# Top.net
KiCad netlist of a schematic drawn in Altium Designer
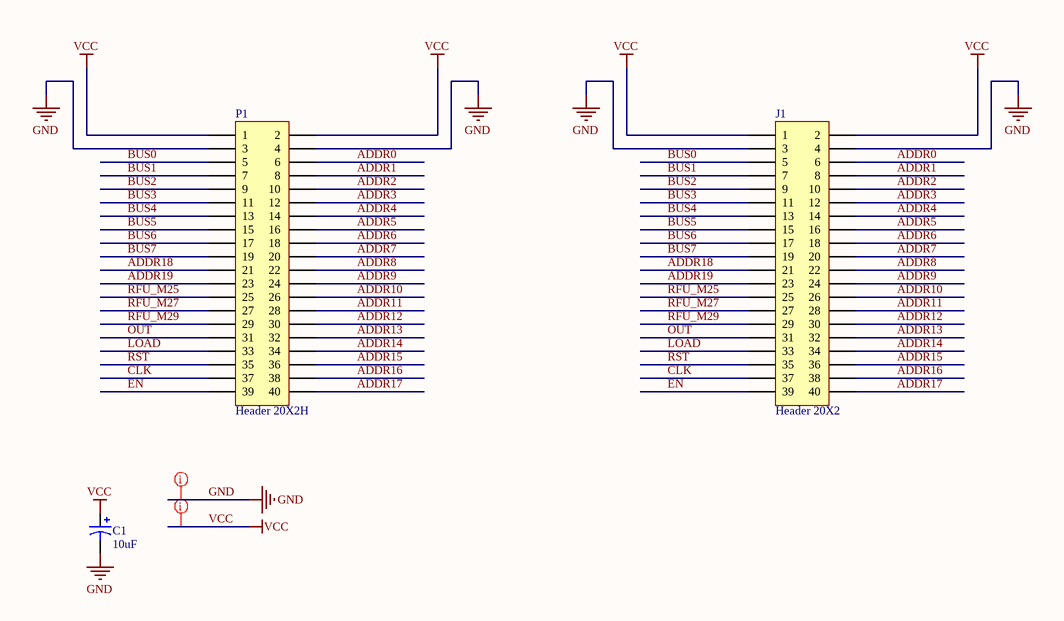
[diagram p0: Top.SchDoc]

(export (version "E")
  (design (tool "Eeschema 10.0.6"))
  (components
    (comp (ref "C1")
      (value "10uF")
      (footprint "C5x7")
      (description "Polarized Capacitor")
      (fields (field (name "Comment") "Cap Pol5") (field (name "PUBLISHER") "Altium Limited"))
      (libsource (lib "Miscellaneous Devices") (part "Cap Pol5"))
    )
    (comp (ref "J1")
      (value "Header 20X2")
      (footprint "HDR2X20")
      (description "Header, 20-Pin, Dual row")
      (fields (field (name "PUBLISHER") "Altium Limited"))
      (libsource (lib "Miscellaneous Connectors") (part "Header 20X2"))
    )
    (comp (ref "P1")
      (value "Header 20X2H")
      (footprint "HDR2X20H")
      (description "Header, 20-Pin, Dual row, Right Angle")
      (fields (field (name "PUBLISHER") "Altium Limited"))
      (libsource (lib "Miscellaneous Connectors") (part "Header 20X2H"))
    )
  )
  (nets
    (net (code "1") (name "/ADDR0") (class "Default")
      (node (ref "J1") (pin "6") (pinfunction "6_6") (pintype "passive"))
      (node (ref "P1") (pin "6") (pinfunction "6_6") (pintype "passive"))
    )
    (net (code "2") (name "/ADDR1") (class "Default")
      (node (ref "J1") (pin "8") (pinfunction "8_8") (pintype "passive"))
      (node (ref "P1") (pin "8") (pinfunction "8_8") (pintype "passive"))
    )
    (net (code "3") (name "/ADDR2") (class "Default")
      (node (ref "J1") (pin "10") (pinfunction "10_10") (pintype "passive"))
      (node (ref "P1") (pin "10") (pinfunction "10_10") (pintype "passive"))
    )
    (net (code "4") (name "/ADDR3") (class "Default")
      (node (ref "J1") (pin "12") (pinfunction "12_12") (pintype "passive"))
      (node (ref "P1") (pin "12") (pinfunction "12_12") (pintype "passive"))
    )
    (net (code "5") (name "/ADDR4") (class "Default")
      (node (ref "J1") (pin "14") (pinfunction "14_14") (pintype "passive"))
      (node (ref "P1") (pin "14") (pinfunction "14_14") (pintype "passive"))
    )
    (net (code "6") (name "/ADDR5") (class "Default")
      (node (ref "J1") (pin "16") (pinfunction "16_16") (pintype "passive"))
      (node (ref "P1") (pin "16") (pinfunction "16_16") (pintype "passive"))
    )
    (net (code "7") (name "/ADDR6") (class "Default")
      (node (ref "J1") (pin "18") (pinfunction "18_18") (pintype "passive"))
      (node (ref "P1") (pin "18") (pinfunction "18_18") (pintype "passive"))
    )
    (net (code "8") (name "/ADDR7") (class "Default")
      (node (ref "J1") (pin "20") (pinfunction "20_20") (pintype "passive"))
      (node (ref "P1") (pin "20") (pinfunction "20_20") (pintype "passive"))
    )
    (net (code "9") (name "/ADDR8") (class "Default")
      (node (ref "J1") (pin "22") (pinfunction "22_22") (pintype "passive"))
      (node (ref "P1") (pin "22") (pinfunction "22_22") (pintype "passive"))
    )
    (net (code "10") (name "/ADDR9") (class "Default")
      (node (ref "J1") (pin "24") (pinfunction "24_24") (pintype "passive"))
      (node (ref "P1") (pin "24") (pinfunction "24_24") (pintype "passive"))
    )
    (net (code "11") (name "/ADDR10") (class "Default")
      (node (ref "J1") (pin "26") (pinfunction "26_26") (pintype "passive"))
      (node (ref "P1") (pin "26") (pinfunction "26_26") (pintype "passive"))
    )
    (net (code "12") (name "/ADDR11") (class "Default")
      (node (ref "J1") (pin "28") (pinfunction "28_28") (pintype "passive"))
      (node (ref "P1") (pin "28") (pinfunction "28_28") (pintype "passive"))
    )
    (net (code "13") (name "/ADDR12") (class "Default")
      (node (ref "J1") (pin "30") (pinfunction "30_30") (pintype "passive"))
      (node (ref "P1") (pin "30") (pinfunction "30_30") (pintype "passive"))
    )
    (net (code "14") (name "/ADDR13") (class "Default")
      (node (ref "J1") (pin "32") (pinfunction "32_32") (pintype "passive"))
      (node (ref "P1") (pin "32") (pinfunction "32_32") (pintype "passive"))
    )
    (net (code "15") (name "/ADDR14") (class "Default")
      (node (ref "J1") (pin "34") (pinfunction "34_34") (pintype "passive"))
      (node (ref "P1") (pin "34") (pinfunction "34_34") (pintype "passive"))
    )
    (net (code "16") (name "/ADDR15") (class "Default")
      (node (ref "J1") (pin "36") (pinfunction "36_36") (pintype "passive"))
      (node (ref "P1") (pin "36") (pinfunction "36_36") (pintype "passive"))
    )
    (net (code "17") (name "/ADDR16") (class "Default")
      (node (ref "J1") (pin "38") (pinfunction "38_38") (pintype "passive"))
      (node (ref "P1") (pin "38") (pinfunction "38_38") (pintype "passive"))
    )
    (net (code "18") (name "/ADDR17") (class "Default")
      (node (ref "J1") (pin "40") (pinfunction "40_40") (pintype "passive"))
      (node (ref "P1") (pin "40") (pinfunction "40_40") (pintype "passive"))
    )
    (net (code "19") (name "/ADDR18") (class "Default")
      (node (ref "J1") (pin "21") (pinfunction "21_21") (pintype "passive"))
      (node (ref "P1") (pin "21") (pinfunction "21_21") (pintype "passive"))
    )
    (net (code "20") (name "/ADDR19") (class "Default")
      (node (ref "J1") (pin "23") (pinfunction "23_23") (pintype "passive"))
      (node (ref "P1") (pin "23") (pinfunction "23_23") (pintype "passive"))
    )
    (net (code "21") (name "/BUS0") (class "Default")
      (node (ref "J1") (pin "5") (pinfunction "5_5") (pintype "passive"))
      (node (ref "P1") (pin "5") (pinfunction "5_5") (pintype "passive"))
    )
    (net (code "22") (name "/BUS1") (class "Default")
      (node (ref "J1") (pin "7") (pinfunction "7_7") (pintype "passive"))
      (node (ref "P1") (pin "7") (pinfunction "7_7") (pintype "passive"))
    )
    (net (code "23") (name "/BUS2") (class "Default")
      (node (ref "J1") (pin "9") (pinfunction "9_9") (pintype "passive"))
      (node (ref "P1") (pin "9") (pinfunction "9_9") (pintype "passive"))
    )
    (net (code "24") (name "/BUS3") (class "Default")
      (node (ref "J1") (pin "11") (pinfunction "11_11") (pintype "passive"))
      (node (ref "P1") (pin "11") (pinfunction "11_11") (pintype "passive"))
    )
    (net (code "25") (name "/BUS4") (class "Default")
      (node (ref "J1") (pin "13") (pinfunction "13_13") (pintype "passive"))
      (node (ref "P1") (pin "13") (pinfunction "13_13") (pintype "passive"))
    )
    (net (code "26") (name "/BUS5") (class "Default")
      (node (ref "J1") (pin "15") (pinfunction "15_15") (pintype "passive"))
      (node (ref "P1") (pin "15") (pinfunction "15_15") (pintype "passive"))
    )
    (net (code "27") (name "/BUS6") (class "Default")
      (node (ref "J1") (pin "17") (pinfunction "17_17") (pintype "passive"))
      (node (ref "P1") (pin "17") (pinfunction "17_17") (pintype "passive"))
    )
    (net (code "28") (name "/BUS7") (class "Default")
      (node (ref "J1") (pin "19") (pinfunction "19_19") (pintype "passive"))
      (node (ref "P1") (pin "19") (pinfunction "19_19") (pintype "passive"))
    )
    (net (code "29") (name "/CLK") (class "Default")
      (node (ref "J1") (pin "37") (pinfunction "37_37") (pintype "passive"))
      (node (ref "P1") (pin "37") (pinfunction "37_37") (pintype "passive"))
    )
    (net (code "30") (name "/EN") (class "Default")
      (node (ref "J1") (pin "39") (pinfunction "39_39") (pintype "passive"))
      (node (ref "P1") (pin "39") (pinfunction "39_39") (pintype "passive"))
    )
    (net (code "31") (name "/LOAD") (class "Default")
      (node (ref "J1") (pin "33") (pinfunction "33_33") (pintype "passive"))
      (node (ref "P1") (pin "33") (pinfunction "33_33") (pintype "passive"))
    )
    (net (code "32") (name "/RFU_M25") (class "Default")
      (node (ref "J1") (pin "25") (pinfunction "25_25") (pintype "passive"))
      (node (ref "P1") (pin "25") (pinfunction "25_25") (pintype "passive"))
    )
    (net (code "33") (name "/RFU_M27") (class "Default")
      (node (ref "J1") (pin "27") (pinfunction "27_27") (pintype "passive"))
      (node (ref "P1") (pin "27") (pinfunction "27_27") (pintype "passive"))
    )
    (net (code "34") (name "/RFU_M29") (class "Default")
      (node (ref "J1") (pin "29") (pinfunction "29_29") (pintype "passive"))
      (node (ref "P1") (pin "29") (pinfunction "29_29") (pintype "passive"))
    )
    (net (code "35") (name "/RST") (class "Default")
      (node (ref "J1") (pin "35") (pinfunction "35_35") (pintype "passive"))
      (node (ref "P1") (pin "35") (pinfunction "35_35") (pintype "passive"))
    )
    (net (code "36") (name "/~{OUT}") (class "Default")
      (node (ref "J1") (pin "31") (pinfunction "31_31") (pintype "passive"))
      (node (ref "P1") (pin "31") (pinfunction "31_31") (pintype "passive"))
    )
    (net (code "37") (name "GND") (class "Default")
      (node (ref "C1") (pin "2") (pinfunction "2_2") (pintype "passive"))
      (node (ref "J1") (pin "3") (pinfunction "3_3") (pintype "passive"))
      (node (ref "J1") (pin "4") (pinfunction "4_4") (pintype "passive"))
      (node (ref "P1") (pin "3") (pinfunction "3_3") (pintype "passive"))
      (node (ref "P1") (pin "4") (pinfunction "4_4") (pintype "passive"))
    )
    (net (code "38") (name "VCC") (class "Default")
      (node (ref "C1") (pin "1") (pinfunction "1_1") (pintype "passive"))
      (node (ref "J1") (pin "1") (pinfunction "1_1") (pintype "passive"))
      (node (ref "J1") (pin "2") (pinfunction "2_2") (pintype "passive"))
      (node (ref "P1") (pin "1") (pinfunction "1_1") (pintype "passive"))
      (node (ref "P1") (pin "2") (pinfunction "2_2") (pintype "passive"))
    )
  )
)
